# 4P-20700-Mod-PCB-BETA.net
KiCad netlist of a schematic drawn in EAGLE
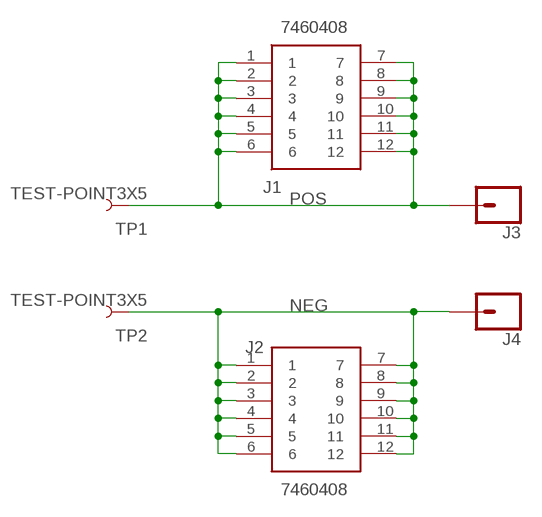
[diagram p0: schematic, sheet 1]

(export (version "E")
  (design (tool "Eeschema 10.0.6"))
  (components
    (comp (ref "J1")
      (value "7460408")
      (footprint "eagle-import:7460408")
      (fields (field (name "MOUSER_PART_NUMBER") "710-7460408"))
      (libsource (lib "eagle-import") (part "7460408"))
    )
    (comp (ref "J2")
      (value "7460408")
      (footprint "eagle-import:7460408")
      (fields (field (name "MOUSER_PART_NUMBER") "710-7460408"))
      (libsource (lib "eagle-import") (part "7460408"))
    )
    (comp (ref "J3")
      (value "CONN_01")
      (footprint "eagle-import:1X01")
      (libsource (lib "eagle-import") (part "CONN_01"))
    )
    (comp (ref "J4")
      (value "CONN_01")
      (footprint "eagle-import:1X01")
      (libsource (lib "eagle-import") (part "CONN_01"))
    )
    (comp (ref "TP1")
      (value "TEST-POINT3X5")
      (footprint "eagle-import:PAD.03X.05")
      (libsource (lib "eagle-import") (part "TEST-POINT3X5"))
    )
    (comp (ref "TP2")
      (value "TEST-POINT3X5")
      (footprint "eagle-import:PAD.03X.05")
      (libsource (lib "eagle-import") (part "TEST-POINT3X5"))
    )
  )
  (nets
    (net (code "1") (name "/NEG") (class "Default")
      (node (ref "J2") (pin "1") (pinfunction "1_1") (pintype "bidirectional"))
      (node (ref "J2") (pin "10") (pinfunction "10_10") (pintype "bidirectional"))
      (node (ref "J2") (pin "11") (pinfunction "11_11") (pintype "bidirectional"))
      (node (ref "J2") (pin "12") (pinfunction "12_12") (pintype "bidirectional"))
      (node (ref "J2") (pin "2") (pinfunction "2_2") (pintype "bidirectional"))
      (node (ref "J2") (pin "3") (pinfunction "3_3") (pintype "bidirectional"))
      (node (ref "J2") (pin "4") (pinfunction "4_4") (pintype "bidirectional"))
      (node (ref "J2") (pin "5") (pinfunction "5_5") (pintype "bidirectional"))
      (node (ref "J2") (pin "6") (pinfunction "6_6") (pintype "bidirectional"))
      (node (ref "J2") (pin "7") (pinfunction "7_7") (pintype "bidirectional"))
      (node (ref "J2") (pin "8") (pinfunction "8_8") (pintype "bidirectional"))
      (node (ref "J2") (pin "9") (pinfunction "9_9") (pintype "bidirectional"))
      (node (ref "J4") (pin "1") (pinfunction "1_1") (pintype "passive"))
      (node (ref "TP2") (pin "P$1") (pinfunction "1_P$1") (pintype "bidirectional"))
    )
    (net (code "2") (name "/POS") (class "Default")
      (node (ref "J1") (pin "1") (pinfunction "1_1") (pintype "bidirectional"))
      (node (ref "J1") (pin "10") (pinfunction "10_10") (pintype "bidirectional"))
      (node (ref "J1") (pin "11") (pinfunction "11_11") (pintype "bidirectional"))
      (node (ref "J1") (pin "12") (pinfunction "12_12") (pintype "bidirectional"))
      (node (ref "J1") (pin "2") (pinfunction "2_2") (pintype "bidirectional"))
      (node (ref "J1") (pin "3") (pinfunction "3_3") (pintype "bidirectional"))
      (node (ref "J1") (pin "4") (pinfunction "4_4") (pintype "bidirectional"))
      (node (ref "J1") (pin "5") (pinfunction "5_5") (pintype "bidirectional"))
      (node (ref "J1") (pin "6") (pinfunction "6_6") (pintype "bidirectional"))
      (node (ref "J1") (pin "7") (pinfunction "7_7") (pintype "bidirectional"))
      (node (ref "J1") (pin "8") (pinfunction "8_8") (pintype "bidirectional"))
      (node (ref "J1") (pin "9") (pinfunction "9_9") (pintype "bidirectional"))
      (node (ref "J3") (pin "1") (pinfunction "1_1") (pintype "passive"))
      (node (ref "TP1") (pin "P$1") (pinfunction "1_P$1") (pintype "bidirectional"))
    )
  )
)
